# arduino-shield-xyz-stepper.net
KiCad netlist of a schematic drawn in EAGLE
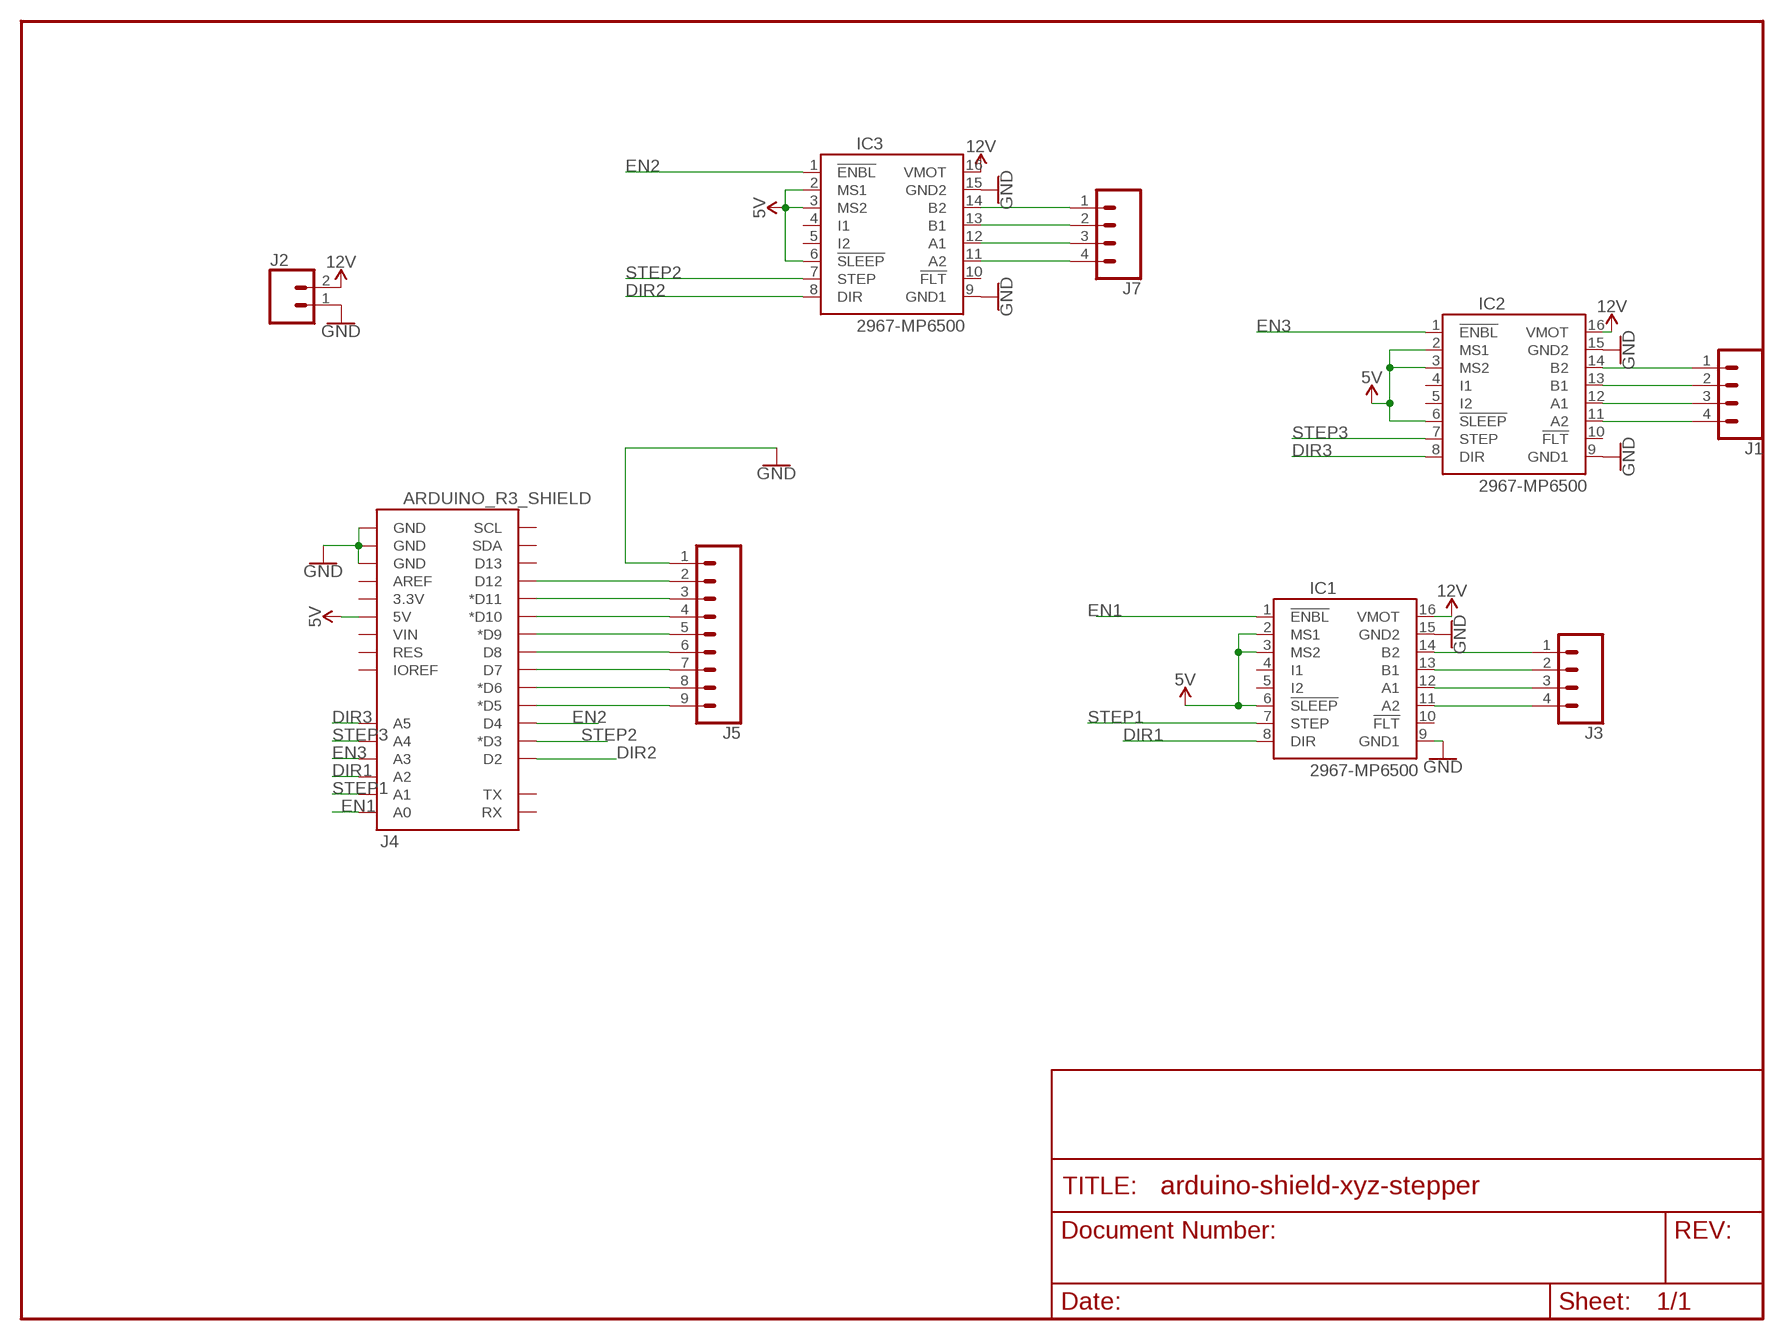
[diagram p0: schematic, sheet 1]

(export (version "E")
  (design (tool "Eeschema 10.0.6"))
  (components
    (comp (ref "IC1")
      (value "2967-MP6500")
      (footprint "eagle-import:MP6500")
      (libsource (lib "eagle-import") (part "2967-MP6500"))
    )
    (comp (ref "IC2")
      (value "2967-MP6500")
      (footprint "eagle-import:MP6500")
      (libsource (lib "eagle-import") (part "2967-MP6500"))
    )
    (comp (ref "IC3")
      (value "2967-MP6500")
      (footprint "eagle-import:MP6500")
      (libsource (lib "eagle-import") (part "2967-MP6500"))
    )
    (comp (ref "J1")
      (value "CONN_04")
      (footprint "eagle-import:1X04")
      (libsource (lib "eagle-import") (part "CONN_04"))
    )
    (comp (ref "J2")
      (value "CONN_02")
      (footprint "eagle-import:1X02")
      (libsource (lib "eagle-import") (part "CONN_02"))
    )
    (comp (ref "J3")
      (value "CONN_04")
      (footprint "eagle-import:1X04")
      (libsource (lib "eagle-import") (part "CONN_04"))
    )
    (comp (ref "J4")
      (value "ARDUINO_R3_SHIELD")
      (footprint "eagle-import:UNO_R3_SHIELD")
      (libsource (lib "eagle-import") (part "ARDUINO_R3_SHIELD"))
    )
    (comp (ref "J5")
      (value "CONN_09")
      (footprint "eagle-import:1X09")
      (libsource (lib "eagle-import") (part "CONN_09"))
    )
    (comp (ref "J7")
      (value "CONN_04")
      (footprint "eagle-import:1X04")
      (libsource (lib "eagle-import") (part "CONN_04"))
    )
  )
  (nets
    (net (code "1") (name "/DIR1") (class "Default")
      (node (ref "IC1") (pin "8") (pinfunction "DIR_8") (pintype "input"))
      (node (ref "J4") (pin "A2") (pinfunction "A2_A2") (pintype "bidirectional"))
    )
    (net (code "2") (name "/DIR2") (class "Default")
      (node (ref "IC3") (pin "8") (pinfunction "DIR_8") (pintype "input"))
      (node (ref "J4") (pin "D2") (pinfunction "D2_D2") (pintype "bidirectional"))
    )
    (net (code "3") (name "/DIR3") (class "Default")
      (node (ref "IC2") (pin "8") (pinfunction "DIR_8") (pintype "input"))
      (node (ref "J4") (pin "A5") (pinfunction "A5_A5") (pintype "bidirectional"))
    )
    (net (code "4") (name "/EN1") (class "Default")
      (node (ref "IC1") (pin "1") (pinfunction "~{ENBL}_1") (pintype "passive"))
      (node (ref "J4") (pin "A0") (pinfunction "A0_A0") (pintype "bidirectional"))
    )
    (net (code "5") (name "/EN2") (class "Default")
      (node (ref "IC3") (pin "1") (pinfunction "~{ENBL}_1") (pintype "passive"))
      (node (ref "J4") (pin "D4") (pinfunction "D4_D4") (pintype "bidirectional"))
    )
    (net (code "6") (name "/EN3") (class "Default")
      (node (ref "IC2") (pin "1") (pinfunction "~{ENBL}_1") (pintype "passive"))
      (node (ref "J4") (pin "A3") (pinfunction "A3_A3") (pintype "bidirectional"))
    )
    (net (code "7") (name "/STEP1") (class "Default")
      (node (ref "IC1") (pin "7") (pinfunction "STEP_7") (pintype "input"))
      (node (ref "J4") (pin "A1") (pinfunction "A1_A1") (pintype "bidirectional"))
    )
    (net (code "8") (name "/STEP2") (class "Default")
      (node (ref "IC3") (pin "7") (pinfunction "STEP_7") (pintype "input"))
      (node (ref "J4") (pin "D3") (pinfunction "*D3_D3") (pintype "bidirectional"))
    )
    (net (code "9") (name "/STEP3") (class "Default")
      (node (ref "IC2") (pin "7") (pinfunction "STEP_7") (pintype "input"))
      (node (ref "J4") (pin "A4") (pinfunction "A4_A4") (pintype "bidirectional"))
    )
    (net (code "10") (name "5V") (class "Default")
      (node (ref "IC1") (pin "2") (pinfunction "MS1_2") (pintype "passive"))
      (node (ref "IC1") (pin "3") (pinfunction "MS2_3") (pintype "passive"))
      (node (ref "IC1") (pin "6") (pinfunction "~{SLEEP}_6") (pintype "input"))
      (node (ref "IC2") (pin "2") (pinfunction "MS1_2") (pintype "passive"))
      (node (ref "IC2") (pin "3") (pinfunction "MS2_3") (pintype "passive"))
      (node (ref "IC2") (pin "6") (pinfunction "~{SLEEP}_6") (pintype "input"))
      (node (ref "IC3") (pin "2") (pinfunction "MS1_2") (pintype "passive"))
      (node (ref "IC3") (pin "3") (pinfunction "MS2_3") (pintype "passive"))
      (node (ref "IC3") (pin "6") (pinfunction "~{SLEEP}_6") (pintype "input"))
      (node (ref "J4") (pin "5V") (pinfunction "5V_5V") (pintype "bidirectional"))
    )
    (net (code "11") (name "12V") (class "Default")
      (node (ref "IC1") (pin "16") (pinfunction "VMOT_16") (pintype "power_in"))
      (node (ref "IC2") (pin "16") (pinfunction "VMOT_16") (pintype "power_in"))
      (node (ref "IC3") (pin "16") (pinfunction "VMOT_16") (pintype "power_in"))
      (node (ref "J2") (pin "2") (pinfunction "2_2") (pintype "passive"))
    )
    (net (code "12") (name "GND") (class "Default")
      (node (ref "IC1") (pin "15") (pinfunction "GND2_15") (pintype "power_in"))
      (node (ref "IC1") (pin "9") (pinfunction "GND1_9") (pintype "power_in"))
      (node (ref "IC2") (pin "15") (pinfunction "GND2_15") (pintype "power_in"))
      (node (ref "IC2") (pin "9") (pinfunction "GND1_9") (pintype "power_in"))
      (node (ref "IC3") (pin "15") (pinfunction "GND2_15") (pintype "power_in"))
      (node (ref "IC3") (pin "9") (pinfunction "GND1_9") (pintype "power_in"))
      (node (ref "J2") (pin "1") (pinfunction "1_1") (pintype "passive"))
      (node (ref "J4") (pin "GND@0") (pinfunction "GND_GND@0") (pintype "bidirectional"))
      (node (ref "J4") (pin "GND@1") (pinfunction "GND_GND@1") (pintype "bidirectional"))
      (node (ref "J4") (pin "GND@2") (pinfunction "GND_GND@2") (pintype "bidirectional"))
      (node (ref "J5") (pin "1") (pinfunction "1_1") (pintype "passive"))
    )
    (net (code "13") (name "Net-(IC1-A1)") (class "Default")
      (node (ref "IC1") (pin "12") (pinfunction "A1_12") (pintype "output"))
      (node (ref "J3") (pin "3") (pinfunction "3_3") (pintype "passive"))
    )
    (net (code "14") (name "Net-(IC1-A2)") (class "Default")
      (node (ref "IC1") (pin "11") (pinfunction "A2_11") (pintype "output"))
      (node (ref "J3") (pin "4") (pinfunction "4_4") (pintype "passive"))
    )
    (net (code "15") (name "Net-(IC1-B1)") (class "Default")
      (node (ref "IC1") (pin "13") (pinfunction "B1_13") (pintype "output"))
      (node (ref "J3") (pin "2") (pinfunction "2_2") (pintype "passive"))
    )
    (net (code "16") (name "Net-(IC1-B2)") (class "Default")
      (node (ref "IC1") (pin "14") (pinfunction "B2_14") (pintype "output"))
      (node (ref "J3") (pin "1") (pinfunction "1_1") (pintype "passive"))
    )
    (net (code "17") (name "Net-(IC2-A1)") (class "Default")
      (node (ref "IC2") (pin "12") (pinfunction "A1_12") (pintype "output"))
      (node (ref "J1") (pin "3") (pinfunction "3_3") (pintype "passive"))
    )
    (net (code "18") (name "Net-(IC2-A2)") (class "Default")
      (node (ref "IC2") (pin "11") (pinfunction "A2_11") (pintype "output"))
      (node (ref "J1") (pin "4") (pinfunction "4_4") (pintype "passive"))
    )
    (net (code "19") (name "Net-(IC2-B1)") (class "Default")
      (node (ref "IC2") (pin "13") (pinfunction "B1_13") (pintype "output"))
      (node (ref "J1") (pin "2") (pinfunction "2_2") (pintype "passive"))
    )
    (net (code "20") (name "Net-(IC2-B2)") (class "Default")
      (node (ref "IC2") (pin "14") (pinfunction "B2_14") (pintype "output"))
      (node (ref "J1") (pin "1") (pinfunction "1_1") (pintype "passive"))
    )
    (net (code "21") (name "Net-(IC3-A1)") (class "Default")
      (node (ref "IC3") (pin "12") (pinfunction "A1_12") (pintype "output"))
      (node (ref "J7") (pin "3") (pinfunction "3_3") (pintype "passive"))
    )
    (net (code "22") (name "Net-(IC3-A2)") (class "Default")
      (node (ref "IC3") (pin "11") (pinfunction "A2_11") (pintype "output"))
      (node (ref "J7") (pin "4") (pinfunction "4_4") (pintype "passive"))
    )
    (net (code "23") (name "Net-(IC3-B1)") (class "Default")
      (node (ref "IC3") (pin "13") (pinfunction "B1_13") (pintype "output"))
      (node (ref "J7") (pin "2") (pinfunction "2_2") (pintype "passive"))
    )
    (net (code "24") (name "Net-(IC3-B2)") (class "Default")
      (node (ref "IC3") (pin "14") (pinfunction "B2_14") (pintype "output"))
      (node (ref "J7") (pin "1") (pinfunction "1_1") (pintype "passive"))
    )
    (net (code "25") (name "Net-(J4-*D5)") (class "Default")
      (node (ref "J4") (pin "D5") (pinfunction "*D5_D5") (pintype "bidirectional"))
      (node (ref "J5") (pin "9") (pinfunction "9_9") (pintype "passive"))
    )
    (net (code "26") (name "Net-(J4-*D6)") (class "Default")
      (node (ref "J4") (pin "D6") (pinfunction "*D6_D6") (pintype "bidirectional"))
      (node (ref "J5") (pin "8") (pinfunction "8_8") (pintype "passive"))
    )
    (net (code "27") (name "Net-(J4-*D9)") (class "Default")
      (node (ref "J4") (pin "D9") (pinfunction "*D9_D9") (pintype "bidirectional"))
      (node (ref "J5") (pin "5") (pinfunction "5_5") (pintype "passive"))
    )
    (net (code "28") (name "Net-(J4-*D10)") (class "Default")
      (node (ref "J4") (pin "D10") (pinfunction "*D10_D10") (pintype "bidirectional"))
      (node (ref "J5") (pin "4") (pinfunction "4_4") (pintype "passive"))
    )
    (net (code "29") (name "Net-(J4-*D11)") (class "Default")
      (node (ref "J4") (pin "D11") (pinfunction "*D11_D11") (pintype "bidirectional"))
      (node (ref "J5") (pin "3") (pinfunction "3_3") (pintype "passive"))
    )
    (net (code "30") (name "Net-(J4-PadD7)") (class "Default")
      (node (ref "J4") (pin "D7") (pinfunction "D7_D7") (pintype "bidirectional"))
      (node (ref "J5") (pin "7") (pinfunction "7_7") (pintype "passive"))
    )
    (net (code "31") (name "Net-(J4-PadD8)") (class "Default")
      (node (ref "J4") (pin "D8") (pinfunction "D8_D8") (pintype "bidirectional"))
      (node (ref "J5") (pin "6") (pinfunction "6_6") (pintype "passive"))
    )
    (net (code "32") (name "Net-(J4-PadD12)") (class "Default")
      (node (ref "J4") (pin "D12") (pinfunction "D12_D12") (pintype "bidirectional"))
      (node (ref "J5") (pin "2") (pinfunction "2_2") (pintype "passive"))
    )
    (net (code "33") (name "unconnected-(IC1-I1-Pad4)") (class "Default")
      (node (ref "IC1") (pin "4") (pinfunction "I1_4") (pintype "passive"))
    )
    (net (code "34") (name "unconnected-(IC1-I2-Pad5)") (class "Default")
      (node (ref "IC1") (pin "5") (pinfunction "I2_5") (pintype "passive"))
    )
    (net (code "35") (name "unconnected-(IC1-~{FLT}-Pad10)") (class "Default")
      (node (ref "IC1") (pin "10") (pinfunction "~{FLT}_10") (pintype "open_collector"))
    )
    (net (code "36") (name "unconnected-(IC2-I1-Pad4)") (class "Default")
      (node (ref "IC2") (pin "4") (pinfunction "I1_4") (pintype "passive"))
    )
    (net (code "37") (name "unconnected-(IC2-I2-Pad5)") (class "Default")
      (node (ref "IC2") (pin "5") (pinfunction "I2_5") (pintype "passive"))
    )
    (net (code "38") (name "unconnected-(IC2-~{FLT}-Pad10)") (class "Default")
      (node (ref "IC2") (pin "10") (pinfunction "~{FLT}_10") (pintype "open_collector"))
    )
    (net (code "39") (name "unconnected-(IC3-I1-Pad4)") (class "Default")
      (node (ref "IC3") (pin "4") (pinfunction "I1_4") (pintype "passive"))
    )
    (net (code "40") (name "unconnected-(IC3-I2-Pad5)") (class "Default")
      (node (ref "IC3") (pin "5") (pinfunction "I2_5") (pintype "passive"))
    )
    (net (code "41") (name "unconnected-(IC3-~{FLT}-Pad10)") (class "Default")
      (node (ref "IC3") (pin "10") (pinfunction "~{FLT}_10") (pintype "open_collector"))
    )
    (net (code "42") (name "unconnected-(J4-Pad3.3V)") (class "Default")
      (node (ref "J4") (pin "3.3V") (pinfunction "3.3V_3.3V") (pintype "bidirectional"))
    )
    (net (code "43") (name "unconnected-(J4-PadAREF)") (class "Default")
      (node (ref "J4") (pin "AREF") (pinfunction "AREF_AREF") (pintype "bidirectional"))
    )
    (net (code "44") (name "unconnected-(J4-PadD13)") (class "Default")
      (node (ref "J4") (pin "D13") (pinfunction "D13_D13") (pintype "bidirectional"))
    )
    (net (code "45") (name "unconnected-(J4-PadIOREF)") (class "Default")
      (node (ref "J4") (pin "IOREF") (pinfunction "IOREF_IOREF") (pintype "bidirectional"))
    )
    (net (code "46") (name "unconnected-(J4-PadRES)") (class "Default")
      (node (ref "J4") (pin "RES") (pinfunction "RES_RES") (pintype "bidirectional"))
    )
    (net (code "47") (name "unconnected-(J4-PadRX)") (class "Default")
      (node (ref "J4") (pin "RX") (pinfunction "RX_RX") (pintype "bidirectional"))
    )
    (net (code "48") (name "unconnected-(J4-PadSCL)") (class "Default")
      (node (ref "J4") (pin "SCL") (pinfunction "SCL_SCL") (pintype "bidirectional"))
    )
    (net (code "49") (name "unconnected-(J4-PadSDA)") (class "Default")
      (node (ref "J4") (pin "SDA") (pinfunction "SDA_SDA") (pintype "bidirectional"))
    )
    (net (code "50") (name "unconnected-(J4-PadTX)") (class "Default")
      (node (ref "J4") (pin "TX") (pinfunction "TX_TX") (pintype "bidirectional"))
    )
    (net (code "51") (name "unconnected-(J4-PadVIN)") (class "Default")
      (node (ref "J4") (pin "VIN") (pinfunction "VIN_VIN") (pintype "bidirectional"))
    )
  )
)
